# Sheet_1.net
KiCad netlist of a schematic drawn in EasyEDA
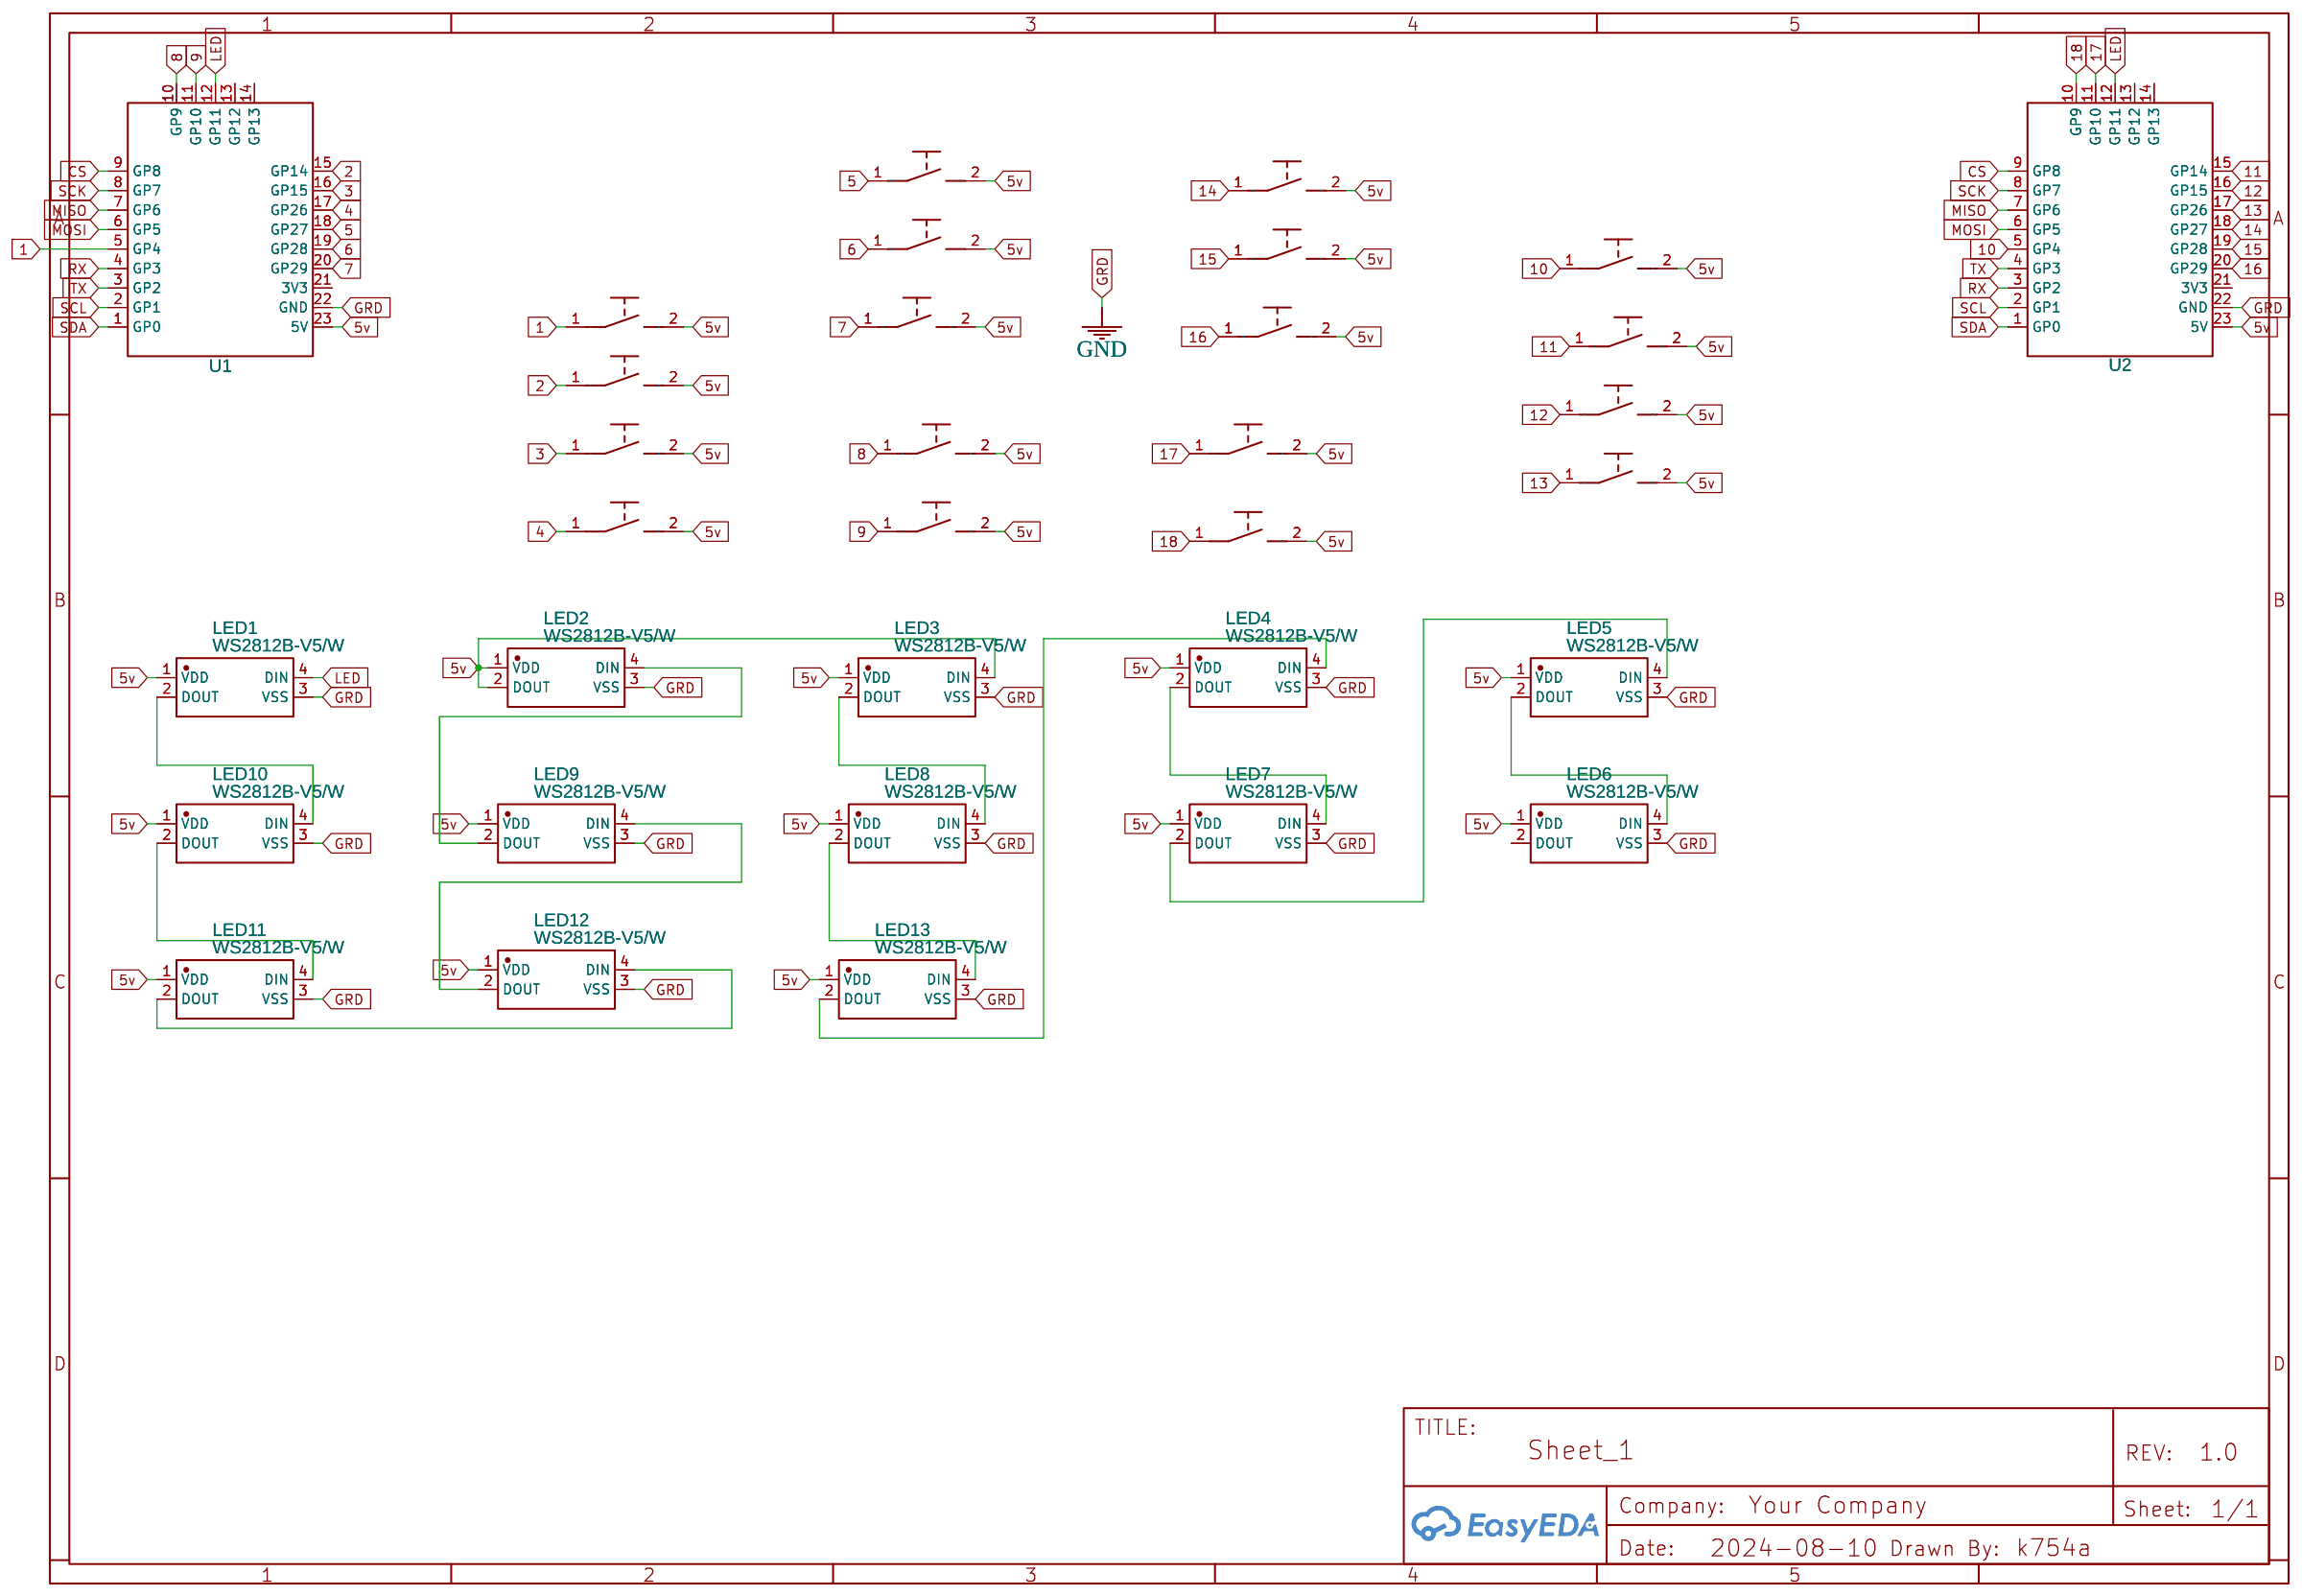
[diagram p0: schematic sheet]

(export (version "E")
  (design (tool "Eeschema 10.0.6"))
  (components
    (comp (ref "LED1")
      (value "WS2812B-V5/W")
      (fields (field (name "Manufacturer") "worldsemi"))
      (libsource (lib "") (part "WS2812B-V5/W"))
    )
    (comp (ref "LED2")
      (value "WS2812B-V5/W")
      (fields (field (name "Manufacturer") "worldsemi"))
      (libsource (lib "") (part "WS2812B-V5/W"))
    )
    (comp (ref "LED3")
      (value "WS2812B-V5/W")
      (fields (field (name "Manufacturer") "worldsemi"))
      (libsource (lib "") (part "WS2812B-V5/W"))
    )
    (comp (ref "LED4")
      (value "WS2812B-V5/W")
      (fields (field (name "Manufacturer") "worldsemi"))
      (libsource (lib "") (part "WS2812B-V5/W"))
    )
    (comp (ref "LED5")
      (value "WS2812B-V5/W")
      (fields (field (name "Manufacturer") "worldsemi"))
      (libsource (lib "") (part "WS2812B-V5/W"))
    )
    (comp (ref "LED6")
      (value "WS2812B-V5/W")
      (fields (field (name "Manufacturer") "worldsemi"))
      (libsource (lib "") (part "WS2812B-V5/W"))
    )
    (comp (ref "LED7")
      (value "WS2812B-V5/W")
      (fields (field (name "Manufacturer") "worldsemi"))
      (libsource (lib "") (part "WS2812B-V5/W"))
    )
    (comp (ref "LED8")
      (value "WS2812B-V5/W")
      (fields (field (name "Manufacturer") "worldsemi"))
      (libsource (lib "") (part "WS2812B-V5/W"))
    )
    (comp (ref "LED9")
      (value "WS2812B-V5/W")
      (fields (field (name "Manufacturer") "worldsemi"))
      (libsource (lib "") (part "WS2812B-V5/W"))
    )
    (comp (ref "LED10")
      (value "WS2812B-V5/W")
      (fields (field (name "Manufacturer") "worldsemi"))
      (libsource (lib "") (part "WS2812B-V5/W"))
    )
    (comp (ref "LED11")
      (value "WS2812B-V5/W")
      (fields (field (name "Manufacturer") "worldsemi"))
      (libsource (lib "") (part "WS2812B-V5/W"))
    )
    (comp (ref "LED12")
      (value "WS2812B-V5/W")
      (fields (field (name "Manufacturer") "worldsemi"))
      (libsource (lib "") (part "WS2812B-V5/W"))
    )
    (comp (ref "LED13")
      (value "WS2812B-V5/W")
      (fields (field (name "Manufacturer") "worldsemi"))
      (libsource (lib "") (part "WS2812B-V5/W"))
    )
    (comp (ref "SW1")
      (value "CPG151101S13")
      (fields (field (name "Manufacturer") "Kailh(凯华)"))
      (libsource (lib "") (part "CPG151101S13"))
    )
    (comp (ref "SW2")
      (value "CPG151101S13")
      (fields (field (name "Manufacturer") "Kailh(凯华)"))
      (libsource (lib "") (part "CPG151101S13"))
    )
    (comp (ref "SW3")
      (value "CPG151101S13")
      (fields (field (name "Manufacturer") "Kailh(凯华)"))
      (libsource (lib "") (part "CPG151101S13"))
    )
    (comp (ref "SW4")
      (value "CPG151101S13")
      (fields (field (name "Manufacturer") "Kailh(凯华)"))
      (libsource (lib "") (part "CPG151101S13"))
    )
    (comp (ref "SW5")
      (value "CPG151101S13")
      (fields (field (name "Manufacturer") "Kailh(凯华)"))
      (libsource (lib "") (part "CPG151101S13"))
    )
    (comp (ref "SW6")
      (value "CPG151101S13")
      (fields (field (name "Manufacturer") "Kailh(凯华)"))
      (libsource (lib "") (part "CPG151101S13"))
    )
    (comp (ref "SW7")
      (value "CPG151101S13")
      (fields (field (name "Manufacturer") "Kailh(凯华)"))
      (libsource (lib "") (part "CPG151101S13"))
    )
    (comp (ref "SW8")
      (value "CPG151101S13")
      (fields (field (name "Manufacturer") "Kailh(凯华)"))
      (libsource (lib "") (part "CPG151101S13"))
    )
    (comp (ref "SW9")
      (value "CPG151101S13")
      (fields (field (name "Manufacturer") "Kailh(凯华)"))
      (libsource (lib "") (part "CPG151101S13"))
    )
    (comp (ref "SW10")
      (value "CPG151101S13")
      (fields (field (name "Manufacturer") "Kailh(凯华)"))
      (libsource (lib "") (part "CPG151101S13"))
    )
    (comp (ref "SW11")
      (value "CPG151101S13")
      (fields (field (name "Manufacturer") "Kailh(凯华)"))
      (libsource (lib "") (part "CPG151101S13"))
    )
    (comp (ref "SW12")
      (value "CPG151101S13")
      (fields (field (name "Manufacturer") "Kailh(凯华)"))
      (libsource (lib "") (part "CPG151101S13"))
    )
    (comp (ref "SW13")
      (value "CPG151101S13")
      (fields (field (name "Manufacturer") "Kailh(凯华)"))
      (libsource (lib "") (part "CPG151101S13"))
    )
    (comp (ref "SW14")
      (value "CPG151101S13")
      (fields (field (name "Manufacturer") "Kailh(凯华)"))
      (libsource (lib "") (part "CPG151101S13"))
    )
    (comp (ref "SW15")
      (value "CPG151101S13")
      (fields (field (name "Manufacturer") "Kailh(凯华)"))
      (libsource (lib "") (part "CPG151101S13"))
    )
    (comp (ref "SW16")
      (value "CPG151101S13")
      (fields (field (name "Manufacturer") "Kailh(凯华)"))
      (libsource (lib "") (part "CPG151101S13"))
    )
    (comp (ref "SW17")
      (value "CPG151101S13")
      (fields (field (name "Manufacturer") "Kailh(凯华)"))
      (libsource (lib "") (part "CPG151101S13"))
    )
    (comp (ref "SW18")
      (value "CPG151101S13")
      (fields (field (name "Manufacturer") "Kailh(凯华)"))
      (libsource (lib "") (part "CPG151101S13"))
    )
    (comp (ref "U1")
      (value "RP2040-ZERO")
      (fields
        (field (name "Manufacturer Part") "RP2040-Zero")
        (field (name "Manufacturer") "Waveshare(微雪电子)")
      )
      (libsource (lib "") (part "RP2040-ZERO"))
    )
    (comp (ref "U2")
      (value "RP2040-ZERO")
      (fields
        (field (name "Manufacturer Part") "RP2040-Zero")
        (field (name "Manufacturer") "Waveshare(微雪电子)")
      )
      (libsource (lib "") (part "RP2040-ZERO"))
    )
  )
  (nets
    (net (code "1") (name "1") (class "Default")
      (node (ref "SW1") (pin "1") (pinfunction "1_1") (pintype "unspecified"))
      (node (ref "U1") (pin "5") (pinfunction "GP4_5") (pintype "unspecified"))
    )
    (net (code "2") (name "2") (class "Default")
      (node (ref "SW2") (pin "1") (pinfunction "1_1") (pintype "unspecified"))
      (node (ref "U1") (pin "15") (pinfunction "GP14_15") (pintype "unspecified"))
    )
    (net (code "3") (name "3") (class "Default")
      (node (ref "SW3") (pin "1") (pinfunction "1_1") (pintype "unspecified"))
      (node (ref "U1") (pin "16") (pinfunction "GP15_16") (pintype "unspecified"))
    )
    (net (code "4") (name "4") (class "Default")
      (node (ref "SW4") (pin "1") (pinfunction "1_1") (pintype "unspecified"))
      (node (ref "U1") (pin "17") (pinfunction "GP26_17") (pintype "unspecified"))
    )
    (net (code "5") (name "5") (class "Default")
      (node (ref "SW5") (pin "1") (pinfunction "1_1") (pintype "unspecified"))
      (node (ref "U1") (pin "18") (pinfunction "GP27_18") (pintype "unspecified"))
    )
    (net (code "6") (name "5v") (class "Default")
      (node (ref "LED1") (pin "1") (pinfunction "VDD_1") (pintype "unspecified"))
      (node (ref "LED10") (pin "1") (pinfunction "VDD_1") (pintype "unspecified"))
      (node (ref "LED11") (pin "1") (pinfunction "VDD_1") (pintype "unspecified"))
      (node (ref "LED12") (pin "1") (pinfunction "VDD_1") (pintype "unspecified"))
      (node (ref "LED13") (pin "1") (pinfunction "VDD_1") (pintype "unspecified"))
      (node (ref "LED2") (pin "1") (pinfunction "VDD_1") (pintype "unspecified"))
      (node (ref "LED2") (pin "2") (pinfunction "DOUT_2") (pintype "unspecified"))
      (node (ref "LED3") (pin "1") (pinfunction "VDD_1") (pintype "unspecified"))
      (node (ref "LED3") (pin "4") (pinfunction "DIN_4") (pintype "unspecified"))
      (node (ref "LED4") (pin "1") (pinfunction "VDD_1") (pintype "unspecified"))
      (node (ref "LED5") (pin "1") (pinfunction "VDD_1") (pintype "unspecified"))
      (node (ref "LED6") (pin "1") (pinfunction "VDD_1") (pintype "unspecified"))
      (node (ref "LED7") (pin "1") (pinfunction "VDD_1") (pintype "unspecified"))
      (node (ref "LED8") (pin "1") (pinfunction "VDD_1") (pintype "unspecified"))
      (node (ref "LED9") (pin "1") (pinfunction "VDD_1") (pintype "unspecified"))
      (node (ref "SW1") (pin "2") (pinfunction "2_2") (pintype "unspecified"))
      (node (ref "SW10") (pin "2") (pinfunction "2_2") (pintype "unspecified"))
      (node (ref "SW11") (pin "2") (pinfunction "2_2") (pintype "unspecified"))
      (node (ref "SW12") (pin "2") (pinfunction "2_2") (pintype "unspecified"))
      (node (ref "SW13") (pin "2") (pinfunction "2_2") (pintype "unspecified"))
      (node (ref "SW14") (pin "2") (pinfunction "2_2") (pintype "unspecified"))
      (node (ref "SW15") (pin "2") (pinfunction "2_2") (pintype "unspecified"))
      (node (ref "SW16") (pin "2") (pinfunction "2_2") (pintype "unspecified"))
      (node (ref "SW17") (pin "2") (pinfunction "2_2") (pintype "unspecified"))
      (node (ref "SW18") (pin "2") (pinfunction "2_2") (pintype "unspecified"))
      (node (ref "SW2") (pin "2") (pinfunction "2_2") (pintype "unspecified"))
      (node (ref "SW3") (pin "2") (pinfunction "2_2") (pintype "unspecified"))
      (node (ref "SW4") (pin "2") (pinfunction "2_2") (pintype "unspecified"))
      (node (ref "SW5") (pin "2") (pinfunction "2_2") (pintype "unspecified"))
      (node (ref "SW6") (pin "2") (pinfunction "2_2") (pintype "unspecified"))
      (node (ref "SW7") (pin "2") (pinfunction "2_2") (pintype "unspecified"))
      (node (ref "SW8") (pin "2") (pinfunction "2_2") (pintype "unspecified"))
      (node (ref "SW9") (pin "2") (pinfunction "2_2") (pintype "unspecified"))
      (node (ref "U1") (pin "23") (pinfunction "5V_23") (pintype "unspecified"))
      (node (ref "U2") (pin "23") (pinfunction "5V_23") (pintype "unspecified"))
    )
    (net (code "7") (name "6") (class "Default")
      (node (ref "SW6") (pin "1") (pinfunction "1_1") (pintype "unspecified"))
      (node (ref "U1") (pin "19") (pinfunction "GP28_19") (pintype "unspecified"))
    )
    (net (code "8") (name "7") (class "Default")
      (node (ref "SW7") (pin "1") (pinfunction "1_1") (pintype "unspecified"))
      (node (ref "U1") (pin "20") (pinfunction "GP29_20") (pintype "unspecified"))
    )
    (net (code "9") (name "8") (class "Default")
      (node (ref "SW8") (pin "1") (pinfunction "1_1") (pintype "unspecified"))
      (node (ref "U1") (pin "10") (pinfunction "GP9_10") (pintype "unspecified"))
    )
    (net (code "10") (name "9") (class "Default")
      (node (ref "SW9") (pin "1") (pinfunction "1_1") (pintype "unspecified"))
      (node (ref "U1") (pin "11") (pinfunction "GP10_11") (pintype "unspecified"))
    )
    (net (code "11") (name "10") (class "Default")
      (node (ref "SW18") (pin "1") (pinfunction "1_1") (pintype "unspecified"))
      (node (ref "U2") (pin "5") (pinfunction "GP4_5") (pintype "unspecified"))
    )
    (net (code "12") (name "11") (class "Default")
      (node (ref "SW17") (pin "1") (pinfunction "1_1") (pintype "unspecified"))
      (node (ref "U2") (pin "15") (pinfunction "GP14_15") (pintype "unspecified"))
    )
    (net (code "13") (name "12") (class "Default")
      (node (ref "SW16") (pin "1") (pinfunction "1_1") (pintype "unspecified"))
      (node (ref "U2") (pin "16") (pinfunction "GP15_16") (pintype "unspecified"))
    )
    (net (code "14") (name "13") (class "Default")
      (node (ref "SW10") (pin "1") (pinfunction "1_1") (pintype "unspecified"))
      (node (ref "U2") (pin "17") (pinfunction "GP26_17") (pintype "unspecified"))
    )
    (net (code "15") (name "14") (class "Default")
      (node (ref "SW14") (pin "1") (pinfunction "1_1") (pintype "unspecified"))
      (node (ref "U2") (pin "18") (pinfunction "GP27_18") (pintype "unspecified"))
    )
    (net (code "16") (name "15") (class "Default")
      (node (ref "SW13") (pin "1") (pinfunction "1_1") (pintype "unspecified"))
      (node (ref "U2") (pin "19") (pinfunction "GP28_19") (pintype "unspecified"))
    )
    (net (code "17") (name "16") (class "Default")
      (node (ref "SW12") (pin "1") (pinfunction "1_1") (pintype "unspecified"))
      (node (ref "U2") (pin "20") (pinfunction "GP29_20") (pintype "unspecified"))
    )
    (net (code "18") (name "17") (class "Default")
      (node (ref "SW11") (pin "1") (pinfunction "1_1") (pintype "unspecified"))
      (node (ref "U2") (pin "11") (pinfunction "GP10_11") (pintype "unspecified"))
    )
    (net (code "19") (name "18") (class "Default")
      (node (ref "SW15") (pin "1") (pinfunction "1_1") (pintype "unspecified"))
      (node (ref "U2") (pin "10") (pinfunction "GP9_10") (pintype "unspecified"))
    )
    (net (code "20") (name "CS") (class "Default")
      (node (ref "U1") (pin "9") (pinfunction "GP8_9") (pintype "unspecified"))
      (node (ref "U2") (pin "9") (pinfunction "GP8_9") (pintype "unspecified"))
    )
    (net (code "21") (name "GRD") (class "Default")
      (node (ref "LED1") (pin "3") (pinfunction "VSS_3") (pintype "unspecified"))
      (node (ref "LED10") (pin "3") (pinfunction "VSS_3") (pintype "unspecified"))
      (node (ref "LED11") (pin "3") (pinfunction "VSS_3") (pintype "unspecified"))
      (node (ref "LED12") (pin "3") (pinfunction "VSS_3") (pintype "unspecified"))
      (node (ref "LED13") (pin "3") (pinfunction "VSS_3") (pintype "unspecified"))
      (node (ref "LED2") (pin "3") (pinfunction "VSS_3") (pintype "unspecified"))
      (node (ref "LED3") (pin "3") (pinfunction "VSS_3") (pintype "unspecified"))
      (node (ref "LED4") (pin "3") (pinfunction "VSS_3") (pintype "unspecified"))
      (node (ref "LED5") (pin "3") (pinfunction "VSS_3") (pintype "unspecified"))
      (node (ref "LED6") (pin "3") (pinfunction "VSS_3") (pintype "unspecified"))
      (node (ref "LED7") (pin "3") (pinfunction "VSS_3") (pintype "unspecified"))
      (node (ref "LED8") (pin "3") (pinfunction "VSS_3") (pintype "unspecified"))
      (node (ref "LED9") (pin "3") (pinfunction "VSS_3") (pintype "unspecified"))
      (node (ref "U1") (pin "22") (pinfunction "GND_22") (pintype "unspecified"))
      (node (ref "U2") (pin "22") (pinfunction "GND_22") (pintype "unspecified"))
    )
    (net (code "22") (name "LED") (class "Default")
      (node (ref "LED1") (pin "4") (pinfunction "DIN_4") (pintype "unspecified"))
      (node (ref "U1") (pin "12") (pinfunction "GP11_12") (pintype "unspecified"))
      (node (ref "U2") (pin "12") (pinfunction "GP11_12") (pintype "unspecified"))
    )
    (net (code "23") (name "MISO") (class "Default")
      (node (ref "U1") (pin "7") (pinfunction "GP6_7") (pintype "unspecified"))
      (node (ref "U2") (pin "7") (pinfunction "GP6_7") (pintype "unspecified"))
    )
    (net (code "24") (name "MOSI") (class "Default")
      (node (ref "U1") (pin "6") (pinfunction "GP5_6") (pintype "unspecified"))
      (node (ref "U2") (pin "6") (pinfunction "GP5_6") (pintype "unspecified"))
    )
    (net (code "25") (name "Net-(LED1-DOUT)") (class "Default")
      (node (ref "LED1") (pin "2") (pinfunction "DOUT_2") (pintype "unspecified"))
      (node (ref "LED10") (pin "4") (pinfunction "DIN_4") (pintype "unspecified"))
    )
    (net (code "26") (name "Net-(LED2-DIN)") (class "Default")
      (node (ref "LED2") (pin "4") (pinfunction "DIN_4") (pintype "unspecified"))
      (node (ref "LED9") (pin "2") (pinfunction "DOUT_2") (pintype "unspecified"))
    )
    (net (code "27") (name "Net-(LED3-DOUT)") (class "Default")
      (node (ref "LED3") (pin "2") (pinfunction "DOUT_2") (pintype "unspecified"))
      (node (ref "LED8") (pin "4") (pinfunction "DIN_4") (pintype "unspecified"))
    )
    (net (code "28") (name "Net-(LED4-DOUT)") (class "Default")
      (node (ref "LED4") (pin "2") (pinfunction "DOUT_2") (pintype "unspecified"))
      (node (ref "LED7") (pin "4") (pinfunction "DIN_4") (pintype "unspecified"))
    )
    (net (code "29") (name "Net-(LED5-DIN)") (class "Default")
      (node (ref "LED5") (pin "4") (pinfunction "DIN_4") (pintype "unspecified"))
      (node (ref "LED7") (pin "2") (pinfunction "DOUT_2") (pintype "unspecified"))
    )
    (net (code "30") (name "Net-(LED5-DOUT)") (class "Default")
      (node (ref "LED5") (pin "2") (pinfunction "DOUT_2") (pintype "unspecified"))
      (node (ref "LED6") (pin "4") (pinfunction "DIN_4") (pintype "unspecified"))
    )
    (net (code "31") (name "Net-(LED10-DOUT)") (class "Default")
      (node (ref "LED10") (pin "2") (pinfunction "DOUT_2") (pintype "unspecified"))
      (node (ref "LED11") (pin "4") (pinfunction "DIN_4") (pintype "unspecified"))
    )
    (net (code "32") (name "Net-(LED11-DOUT)") (class "Default")
      (node (ref "LED11") (pin "2") (pinfunction "DOUT_2") (pintype "unspecified"))
      (node (ref "LED12") (pin "4") (pinfunction "DIN_4") (pintype "unspecified"))
    )
    (net (code "33") (name "Net-(LED12-DOUT)") (class "Default")
      (node (ref "LED12") (pin "2") (pinfunction "DOUT_2") (pintype "unspecified"))
      (node (ref "LED9") (pin "4") (pinfunction "DIN_4") (pintype "unspecified"))
    )
    (net (code "34") (name "Net-(LED13-DIN)") (class "Default")
      (node (ref "LED13") (pin "4") (pinfunction "DIN_4") (pintype "unspecified"))
      (node (ref "LED8") (pin "2") (pinfunction "DOUT_2") (pintype "unspecified"))
    )
    (net (code "35") (name "Net-(LED13-DOUT)") (class "Default")
      (node (ref "LED13") (pin "2") (pinfunction "DOUT_2") (pintype "unspecified"))
      (node (ref "LED4") (pin "4") (pinfunction "DIN_4") (pintype "unspecified"))
    )
    (net (code "36") (name "RX") (class "Default")
      (node (ref "U1") (pin "4") (pinfunction "GP3_4") (pintype "unspecified"))
      (node (ref "U2") (pin "3") (pinfunction "GP2_3") (pintype "unspecified"))
    )
    (net (code "37") (name "SCK") (class "Default")
      (node (ref "U1") (pin "8") (pinfunction "GP7_8") (pintype "unspecified"))
      (node (ref "U2") (pin "8") (pinfunction "GP7_8") (pintype "unspecified"))
    )
    (net (code "38") (name "SCL") (class "Default")
      (node (ref "U1") (pin "2") (pinfunction "GP1_2") (pintype "unspecified"))
      (node (ref "U2") (pin "2") (pinfunction "GP1_2") (pintype "unspecified"))
    )
    (net (code "39") (name "SDA") (class "Default")
      (node (ref "U1") (pin "1") (pinfunction "GP0_1") (pintype "unspecified"))
      (node (ref "U2") (pin "1") (pinfunction "GP0_1") (pintype "unspecified"))
    )
    (net (code "40") (name "TX") (class "Default")
      (node (ref "U1") (pin "3") (pinfunction "GP2_3") (pintype "unspecified"))
      (node (ref "U2") (pin "4") (pinfunction "GP3_4") (pintype "unspecified"))
    )
    (net (code "41") (name "unconnected-(LED6-DOUT-Pad2)") (class "Default")
      (node (ref "LED6") (pin "2") (pinfunction "DOUT_2") (pintype "unspecified"))
    )
    (net (code "42") (name "unconnected-(U1-3V3-Pad21)") (class "Default")
      (node (ref "U1") (pin "21") (pinfunction "3V3_21") (pintype "unspecified"))
    )
    (net (code "43") (name "unconnected-(U1-GP12-Pad13)") (class "Default")
      (node (ref "U1") (pin "13") (pinfunction "GP12_13") (pintype "unspecified"))
    )
    (net (code "44") (name "unconnected-(U1-GP13-Pad14)") (class "Default")
      (node (ref "U1") (pin "14") (pinfunction "GP13_14") (pintype "unspecified"))
    )
    (net (code "45") (name "unconnected-(U2-3V3-Pad21)") (class "Default")
      (node (ref "U2") (pin "21") (pinfunction "3V3_21") (pintype "unspecified"))
    )
    (net (code "46") (name "unconnected-(U2-GP12-Pad13)") (class "Default")
      (node (ref "U2") (pin "13") (pinfunction "GP12_13") (pintype "unspecified"))
    )
    (net (code "47") (name "unconnected-(U2-GP13-Pad14)") (class "Default")
      (node (ref "U2") (pin "14") (pinfunction "GP13_14") (pintype "unspecified"))
    )
  )
)
